# Two_stage_amp.net
KiCad netlist of a schematic drawn in EAGLE
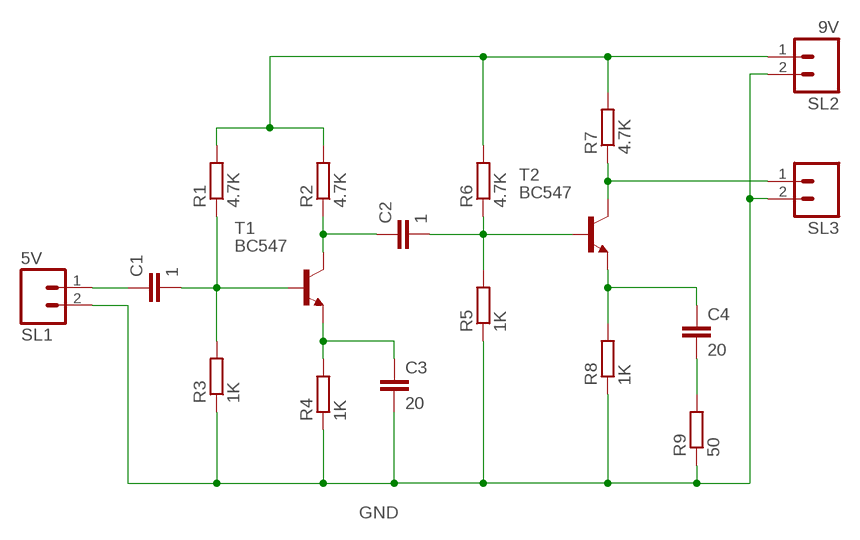
[diagram p0: schematic, sheet 1]

(export (version "E")
  (design (tool "Eeschema 10.0.6"))
  (components
    (comp (ref "C1")
      (value "1")
      (footprint "eagle-import:C025-025X050")
      (libsource (lib "eagle-import") (part "C-EU025-025X050"))
    )
    (comp (ref "C2")
      (value "1")
      (footprint "eagle-import:C025-025X050")
      (libsource (lib "eagle-import") (part "C-EU025-025X050"))
    )
    (comp (ref "C3")
      (value "20")
      (footprint "eagle-import:C025-025X050")
      (libsource (lib "eagle-import") (part "C-EU025-025X050"))
    )
    (comp (ref "C4")
      (value "20")
      (footprint "eagle-import:C025-025X050")
      (libsource (lib "eagle-import") (part "C-EU025-025X050"))
    )
    (comp (ref "R1")
      (value "4.7K")
      (footprint "eagle-import:0204_7")
      (libsource (lib "eagle-import") (part "R-EU_0204/7"))
    )
    (comp (ref "R2")
      (value "4.7K")
      (footprint "eagle-import:0204_7")
      (libsource (lib "eagle-import") (part "R-EU_0204/7"))
    )
    (comp (ref "R3")
      (value "1K")
      (footprint "eagle-import:0204_7")
      (libsource (lib "eagle-import") (part "R-EU_0204/7"))
    )
    (comp (ref "R4")
      (value "1K")
      (footprint "eagle-import:0204_7")
      (libsource (lib "eagle-import") (part "R-EU_0204/7"))
    )
    (comp (ref "R5")
      (value "1K")
      (footprint "eagle-import:0204_7")
      (libsource (lib "eagle-import") (part "R-EU_0204/7"))
    )
    (comp (ref "R6")
      (value "4.7K")
      (footprint "eagle-import:0204_7")
      (libsource (lib "eagle-import") (part "R-EU_0204/7"))
    )
    (comp (ref "R7")
      (value "4.7K")
      (footprint "eagle-import:0204_7")
      (libsource (lib "eagle-import") (part "R-EU_0204/7"))
    )
    (comp (ref "R8")
      (value "1K")
      (footprint "eagle-import:0204_7")
      (libsource (lib "eagle-import") (part "R-EU_0204/7"))
    )
    (comp (ref "R9")
      (value "50")
      (footprint "eagle-import:0204_7")
      (libsource (lib "eagle-import") (part "R-EU_0204/7"))
    )
    (comp (ref "SL1")
      (value "5V")
      (footprint "eagle-import:02P")
      (libsource (lib "eagle-import") (part "M02"))
    )
    (comp (ref "SL2")
      (value "9V")
      (footprint "eagle-import:02P")
      (libsource (lib "eagle-import") (part "M02"))
    )
    (comp (ref "SL3")
      (value "M02")
      (footprint "eagle-import:02P")
      (libsource (lib "eagle-import") (part "M02"))
    )
    (comp (ref "T1")
      (value "BC547")
      (footprint "eagle-import:TO92")
      (libsource (lib "eagle-import") (part "BC547"))
    )
    (comp (ref "T2")
      (value "BC547")
      (footprint "eagle-import:TO92")
      (libsource (lib "eagle-import") (part "BC547"))
    )
  )
  (nets
    (net (code "1") (name "/GND") (class "Default")
      (node (ref "C3") (pin "2") (pinfunction "2_2") (pintype "passive"))
      (node (ref "R3") (pin "1") (pinfunction "1_1") (pintype "passive"))
      (node (ref "R4") (pin "1") (pinfunction "1_1") (pintype "passive"))
      (node (ref "R5") (pin "1") (pinfunction "1_1") (pintype "passive"))
      (node (ref "R8") (pin "1") (pinfunction "1_1") (pintype "passive"))
      (node (ref "R9") (pin "1") (pinfunction "1_1") (pintype "passive"))
      (node (ref "SL1") (pin "2") (pinfunction "2_2") (pintype "passive"))
      (node (ref "SL2") (pin "2") (pinfunction "2_2") (pintype "passive"))
      (node (ref "SL3") (pin "2") (pinfunction "2_2") (pintype "passive"))
    )
    (net (code "2") (name "Net-(C1-Pad1)") (class "Default")
      (node (ref "C1") (pin "1") (pinfunction "1_1") (pintype "passive"))
      (node (ref "SL1") (pin "1") (pinfunction "1_1") (pintype "passive"))
    )
    (net (code "3") (name "Net-(C4-Pad2)") (class "Default")
      (node (ref "C4") (pin "2") (pinfunction "2_2") (pintype "passive"))
      (node (ref "R9") (pin "2") (pinfunction "2_2") (pintype "passive"))
    )
    (net (code "4") (name "Net-(R1-Pad2)") (class "Default")
      (node (ref "R1") (pin "2") (pinfunction "2_2") (pintype "passive"))
      (node (ref "R2") (pin "2") (pinfunction "2_2") (pintype "passive"))
      (node (ref "R6") (pin "2") (pinfunction "2_2") (pintype "passive"))
      (node (ref "R7") (pin "2") (pinfunction "2_2") (pintype "passive"))
      (node (ref "SL2") (pin "1") (pinfunction "1_1") (pintype "passive"))
    )
    (net (code "5") (name "Net-(T1-B)") (class "Default")
      (node (ref "C1") (pin "2") (pinfunction "2_2") (pintype "passive"))
      (node (ref "R1") (pin "1") (pinfunction "1_1") (pintype "passive"))
      (node (ref "R3") (pin "2") (pinfunction "2_2") (pintype "passive"))
      (node (ref "T1") (pin "2") (pinfunction "B_2") (pintype "passive"))
    )
    (net (code "6") (name "Net-(T1-C)") (class "Default")
      (node (ref "C2") (pin "1") (pinfunction "1_1") (pintype "passive"))
      (node (ref "R2") (pin "1") (pinfunction "1_1") (pintype "passive"))
      (node (ref "T1") (pin "3") (pinfunction "C_3") (pintype "passive"))
    )
    (net (code "7") (name "Net-(T1-E)") (class "Default")
      (node (ref "C3") (pin "1") (pinfunction "1_1") (pintype "passive"))
      (node (ref "R4") (pin "2") (pinfunction "2_2") (pintype "passive"))
      (node (ref "T1") (pin "1") (pinfunction "E_1") (pintype "passive"))
    )
    (net (code "8") (name "Net-(T2-B)") (class "Default")
      (node (ref "C2") (pin "2") (pinfunction "2_2") (pintype "passive"))
      (node (ref "R5") (pin "2") (pinfunction "2_2") (pintype "passive"))
      (node (ref "R6") (pin "1") (pinfunction "1_1") (pintype "passive"))
      (node (ref "T2") (pin "2") (pinfunction "B_2") (pintype "passive"))
    )
    (net (code "9") (name "Net-(T2-C)") (class "Default")
      (node (ref "R7") (pin "1") (pinfunction "1_1") (pintype "passive"))
      (node (ref "SL3") (pin "1") (pinfunction "1_1") (pintype "passive"))
      (node (ref "T2") (pin "3") (pinfunction "C_3") (pintype "passive"))
    )
    (net (code "10") (name "Net-(T2-E)") (class "Default")
      (node (ref "C4") (pin "1") (pinfunction "1_1") (pintype "passive"))
      (node (ref "R8") (pin "2") (pinfunction "2_2") (pintype "passive"))
      (node (ref "T2") (pin "1") (pinfunction "E_1") (pintype "passive"))
    )
  )
)
